# Connector-side-2.net
KiCad netlist of a schematic drawn in Altium Designer
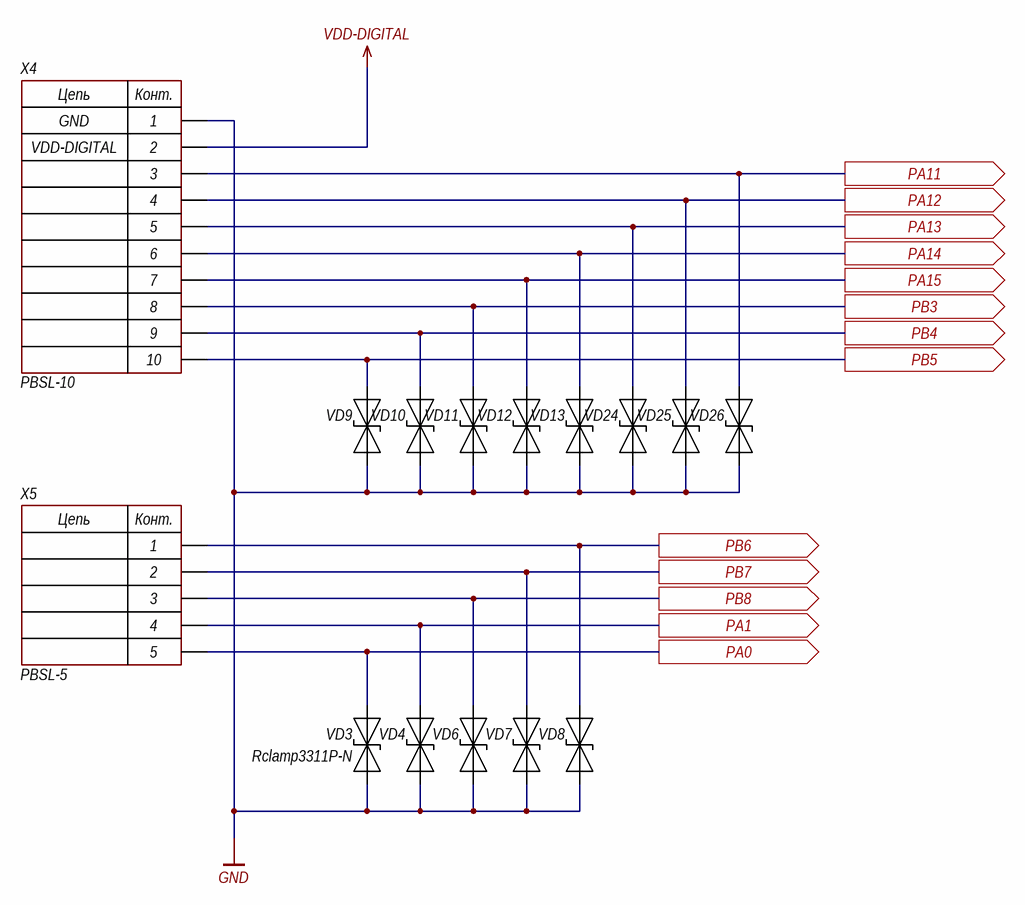
[diagram p0: Connector-side-2.SchDoc]

(export (version "E")
  (design (tool "Eeschema 10.0.6"))
  (components
    (comp (ref "VD3")
      (value "Rclamp3311P-N")
      (footprint "DFN1006-2")
      (fields (field (name "MANUFACTURER") "BORN"))
      (libsource (lib "Diods") (part "TVS-diod"))
    )
    (comp (ref "VD4")
      (value "Rclamp3311P-N")
      (footprint "DFN1006-2")
      (fields (field (name "MANUFACTURER") "BORN"))
      (libsource (lib "Diods") (part "TVS-diod"))
    )
    (comp (ref "VD6")
      (value "Rclamp3311P-N")
      (footprint "DFN1006-2")
      (fields (field (name "MANUFACTURER") "BORN"))
      (libsource (lib "Diods") (part "TVS-diod"))
    )
    (comp (ref "VD7")
      (value "Rclamp3311P-N")
      (footprint "DFN1006-2")
      (fields (field (name "MANUFACTURER") "BORN"))
      (libsource (lib "Diods") (part "TVS-diod"))
    )
    (comp (ref "VD8")
      (value "Rclamp3311P-N")
      (footprint "DFN1006-2")
      (fields (field (name "MANUFACTURER") "BORN"))
      (libsource (lib "Diods") (part "TVS-diod"))
    )
    (comp (ref "VD9")
      (value "Rclamp3311P-N")
      (footprint "DFN1006-2")
      (fields (field (name "MANUFACTURER") "BORN"))
      (libsource (lib "Diods") (part "TVS-diod"))
    )
    (comp (ref "VD10")
      (value "Rclamp3311P-N")
      (footprint "DFN1006-2")
      (fields (field (name "MANUFACTURER") "BORN"))
      (libsource (lib "Diods") (part "TVS-diod"))
    )
    (comp (ref "VD11")
      (value "Rclamp3311P-N")
      (footprint "DFN1006-2")
      (fields (field (name "MANUFACTURER") "BORN"))
      (libsource (lib "Diods") (part "TVS-diod"))
    )
    (comp (ref "VD12")
      (value "Rclamp3311P-N")
      (footprint "DFN1006-2")
      (fields (field (name "MANUFACTURER") "BORN"))
      (libsource (lib "Diods") (part "TVS-diod"))
    )
    (comp (ref "VD13")
      (value "Rclamp3311P-N")
      (footprint "DFN1006-2")
      (fields (field (name "MANUFACTURER") "BORN"))
      (libsource (lib "Diods") (part "TVS-diod"))
    )
    (comp (ref "VD24")
      (value "Rclamp3311P-N")
      (footprint "DFN1006-2")
      (fields (field (name "MANUFACTURER") "BORN"))
      (libsource (lib "Diods") (part "TVS-diod"))
    )
    (comp (ref "VD25")
      (value "Rclamp3311P-N")
      (footprint "DFN1006-2")
      (fields (field (name "MANUFACTURER") "BORN"))
      (libsource (lib "Diods") (part "TVS-diod"))
    )
    (comp (ref "VD26")
      (value "Rclamp3311P-N")
      (footprint "DFN1006-2")
      (fields (field (name "MANUFACTURER") "BORN"))
      (libsource (lib "Diods") (part "TVS-diod"))
    )
    (comp (ref "X4")
      (value "PBSL-10")
      (footprint "CON: PBSL-10")
      (libsource (lib "Connectors") (part "10-Connector"))
    )
    (comp (ref "X5")
      (value "PBSL-5")
      (footprint "CON: PBSL-5")
      (libsource (lib "Connectors") (part "5-Connector"))
    )
  )
  (nets
    (net (code "1") (name "/PA0") (class "Default")
      (node (ref "VD3") (pin "2") (pinfunction "C_2") (pintype "passive"))
      (node (ref "X5") (pin "5") (pinfunction "5_5") (pintype "passive"))
    )
    (net (code "2") (name "/PA1") (class "Default")
      (node (ref "VD4") (pin "2") (pinfunction "C_2") (pintype "passive"))
      (node (ref "X5") (pin "4") (pinfunction "4_4") (pintype "passive"))
    )
    (net (code "3") (name "/PA11") (class "Default")
      (node (ref "VD26") (pin "2") (pinfunction "C_2") (pintype "passive"))
      (node (ref "X4") (pin "3") (pinfunction "3_3") (pintype "passive"))
    )
    (net (code "4") (name "/PA12") (class "Default")
      (node (ref "VD25") (pin "2") (pinfunction "C_2") (pintype "passive"))
      (node (ref "X4") (pin "4") (pinfunction "4_4") (pintype "passive"))
    )
    (net (code "5") (name "/PA13") (class "Default")
      (node (ref "VD24") (pin "2") (pinfunction "C_2") (pintype "passive"))
      (node (ref "X4") (pin "5") (pinfunction "5_5") (pintype "passive"))
    )
    (net (code "6") (name "/PA14") (class "Default")
      (node (ref "VD13") (pin "2") (pinfunction "C_2") (pintype "passive"))
      (node (ref "X4") (pin "6") (pinfunction "6_6") (pintype "passive"))
    )
    (net (code "7") (name "/PA15") (class "Default")
      (node (ref "VD12") (pin "2") (pinfunction "C_2") (pintype "passive"))
      (node (ref "X4") (pin "7") (pinfunction "7_7") (pintype "passive"))
    )
    (net (code "8") (name "/PB3") (class "Default")
      (node (ref "VD11") (pin "2") (pinfunction "C_2") (pintype "passive"))
      (node (ref "X4") (pin "8") (pinfunction "8_8") (pintype "passive"))
    )
    (net (code "9") (name "/PB4") (class "Default")
      (node (ref "VD10") (pin "2") (pinfunction "C_2") (pintype "passive"))
      (node (ref "X4") (pin "9") (pinfunction "9_9") (pintype "passive"))
    )
    (net (code "10") (name "/PB5") (class "Default")
      (node (ref "VD9") (pin "2") (pinfunction "C_2") (pintype "passive"))
      (node (ref "X4") (pin "10") (pinfunction "10_10") (pintype "passive"))
    )
    (net (code "11") (name "/PB6") (class "Default")
      (node (ref "VD8") (pin "2") (pinfunction "C_2") (pintype "passive"))
      (node (ref "X5") (pin "1") (pinfunction "1_1") (pintype "passive"))
    )
    (net (code "12") (name "/PB7") (class "Default")
      (node (ref "VD7") (pin "2") (pinfunction "C_2") (pintype "passive"))
      (node (ref "X5") (pin "2") (pinfunction "2_2") (pintype "passive"))
    )
    (net (code "13") (name "/PB8") (class "Default")
      (node (ref "VD6") (pin "2") (pinfunction "C_2") (pintype "passive"))
      (node (ref "X5") (pin "3") (pinfunction "3_3") (pintype "passive"))
    )
    (net (code "14") (name "GND") (class "Default")
      (node (ref "VD10") (pin "1") (pinfunction "A_1") (pintype "passive"))
      (node (ref "VD11") (pin "1") (pinfunction "A_1") (pintype "passive"))
      (node (ref "VD12") (pin "1") (pinfunction "A_1") (pintype "passive"))
      (node (ref "VD13") (pin "1") (pinfunction "A_1") (pintype "passive"))
      (node (ref "VD24") (pin "1") (pinfunction "A_1") (pintype "passive"))
      (node (ref "VD25") (pin "1") (pinfunction "A_1") (pintype "passive"))
      (node (ref "VD26") (pin "1") (pinfunction "A_1") (pintype "passive"))
      (node (ref "VD3") (pin "1") (pinfunction "A_1") (pintype "passive"))
      (node (ref "VD4") (pin "1") (pinfunction "A_1") (pintype "passive"))
      (node (ref "VD6") (pin "1") (pinfunction "A_1") (pintype "passive"))
      (node (ref "VD7") (pin "1") (pinfunction "A_1") (pintype "passive"))
      (node (ref "VD8") (pin "1") (pinfunction "A_1") (pintype "passive"))
      (node (ref "VD9") (pin "1") (pinfunction "A_1") (pintype "passive"))
      (node (ref "X4") (pin "1") (pinfunction "1_1") (pintype "passive"))
    )
    (net (code "15") (name "VDD-DIGITAL") (class "Default")
      (node (ref "X4") (pin "2") (pinfunction "2_2") (pintype "passive"))
    )
  )
)
